# config-bank7.net
KiCad netlist of a schematic drawn in Altium Designer
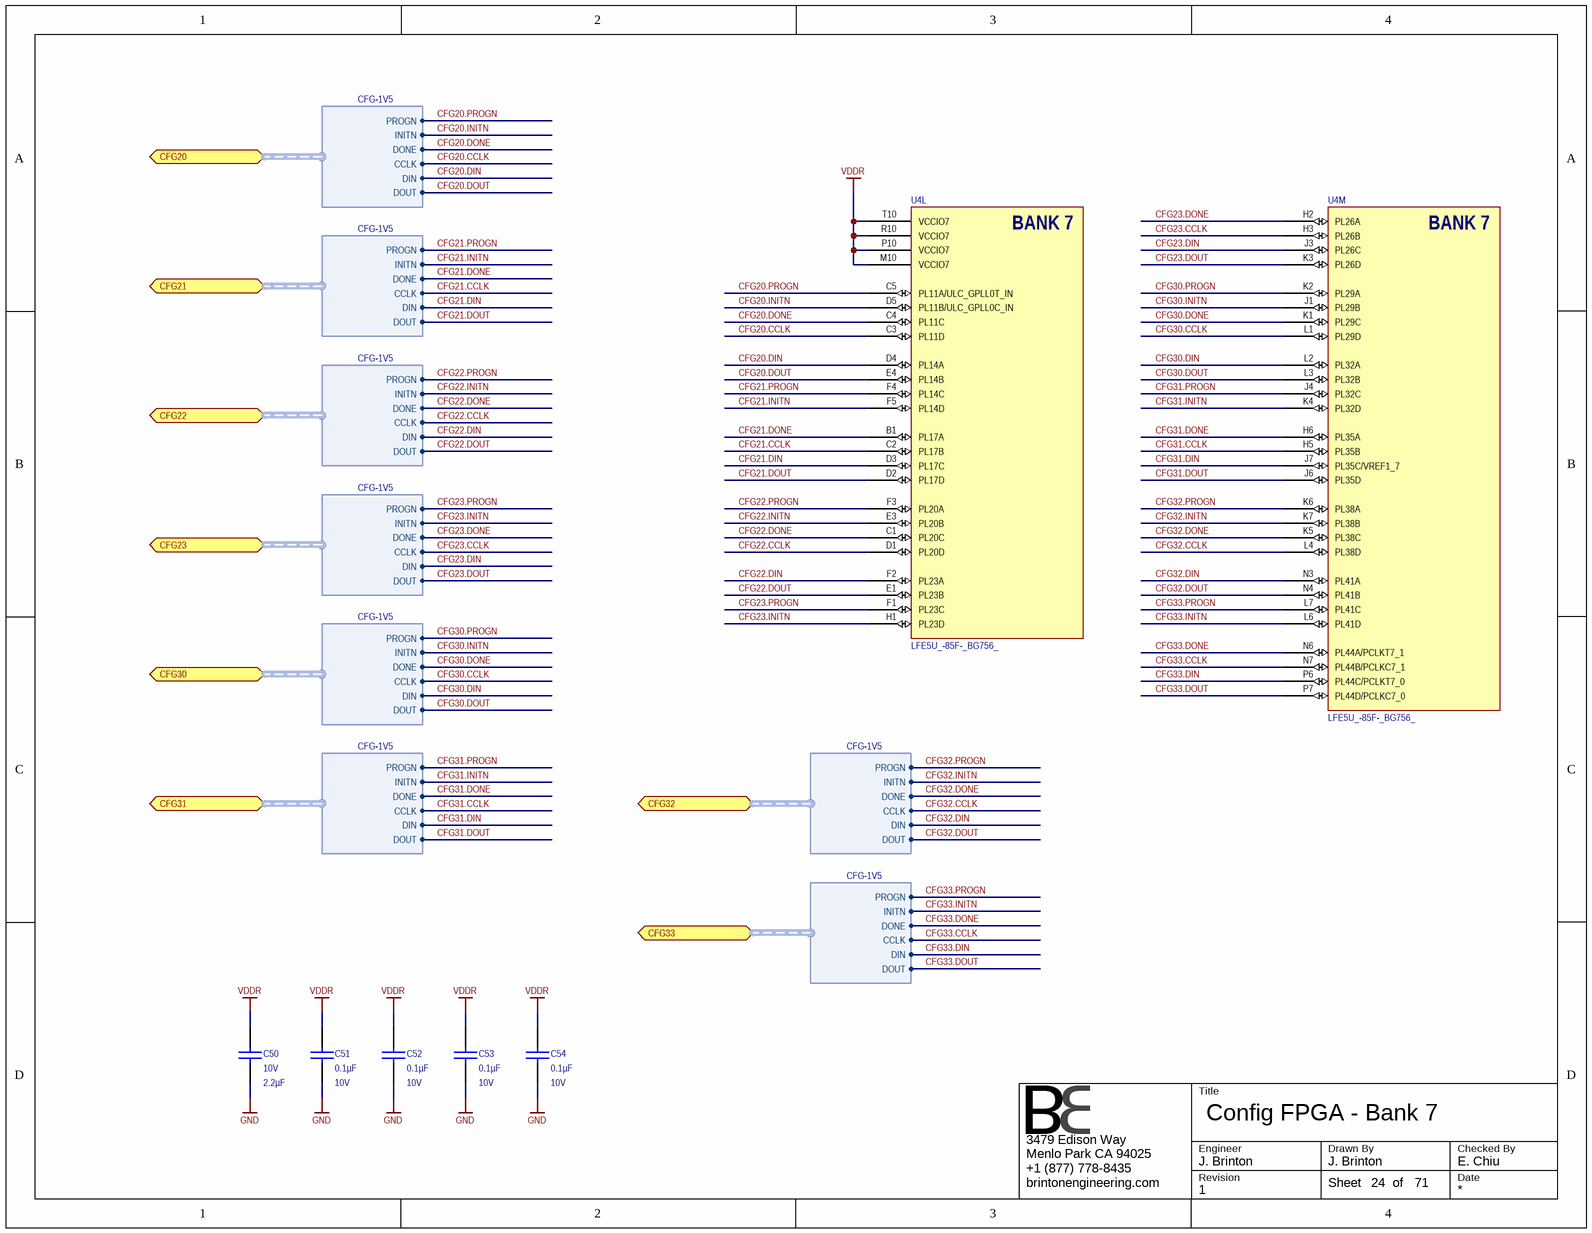
[diagram p0: config-bank7.SchDoc]

(export (version "E")
  (design (tool "Eeschema 10.0.6"))
  (components
    (comp (ref "C50")
      (value "GRM188R71A225KE15D")
      (footprint "CAPC1608X90N")
      (description "CAP CER 2.2UF 10V 10% X7R 0603")
      (fields
        (field (name "MANUFACTURER") "Murata Electronics North America")
        (field (name "TOLERANCE") "±10%")
        (field (name "VOLTAGE - RATED") "10V")
        (field (name "CAPACITANCE") "2.2µF")
      )
      (libsource (lib "murata") (part "GRM188R71A225KE15D"))
    )
    (comp (ref "C51")
      (value "GRM155R71A104KA01J")
      (footprint "CAPC1005X56N")
      (description "CAP CER 0.1UF 10V 10% X7R 0402")
      (fields
        (field (name "MANUFACTURER") "Murata Electronics North America")
        (field (name "TOLERANCE") "±10%")
        (field (name "CAPACITANCE") "0.1µF")
        (field (name "VOLTAGE - RATED") "10V")
      )
      (libsource (lib "murata") (part "GRM155R71A104KA01J"))
    )
    (comp (ref "C52")
      (value "GRM155R71A104KA01J")
      (footprint "CAPC1005X56N")
      (description "CAP CER 0.1UF 10V 10% X7R 0402")
      (fields
        (field (name "MANUFACTURER") "Murata Electronics North America")
        (field (name "TOLERANCE") "±10%")
        (field (name "CAPACITANCE") "0.1µF")
        (field (name "VOLTAGE - RATED") "10V")
      )
      (libsource (lib "murata") (part "GRM155R71A104KA01J"))
    )
    (comp (ref "C53")
      (value "GRM155R71A104KA01J")
      (footprint "CAPC1005X56N")
      (description "CAP CER 0.1UF 10V 10% X7R 0402")
      (fields
        (field (name "MANUFACTURER") "Murata Electronics North America")
        (field (name "TOLERANCE") "±10%")
        (field (name "CAPACITANCE") "0.1µF")
        (field (name "VOLTAGE - RATED") "10V")
      )
      (libsource (lib "murata") (part "GRM155R71A104KA01J"))
    )
    (comp (ref "C54")
      (value "GRM155R71A104KA01J")
      (footprint "CAPC1005X56N")
      (description "CAP CER 0.1UF 10V 10% X7R 0402")
      (fields
        (field (name "MANUFACTURER") "Murata Electronics North America")
        (field (name "TOLERANCE") "±10%")
        (field (name "CAPACITANCE") "0.1µF")
        (field (name "VOLTAGE - RATED") "10V")
      )
      (libsource (lib "murata") (part "GRM155R71A104KA01J"))
    )
    (comp (ref "U4")
      (value "LFE5U_-85F-_BG756_")
      (footprint "lattice:caBGA756")
      (description "ECP5 FPGA, 85k LUT, 756-caBGA")
      (fields (field (name "MANUFACTURER") "Lattice Semiconductor"))
      (libsource (lib "lattice") (part "LFE5U_-85F-_BG756_"))
    )
  )
  (nets
    (net (code "2") (name "/CFG20.CCLK") (class "Default")
      (node (ref "U4") (pin "C3") (pinfunction "PL11D_C3") (pintype "bidirectional"))
    )
    (net (code "3") (name "/CFG20.DIN") (class "Default")
      (node (ref "U4") (pin "D4") (pinfunction "PL14A_D4") (pintype "bidirectional"))
    )
    (net (code "4") (name "/CFG20.DONE") (class "Default")
      (node (ref "U4") (pin "C4") (pinfunction "PL11C_C4") (pintype "bidirectional"))
    )
    (net (code "5") (name "/CFG20.DOUT") (class "Default")
      (node (ref "U4") (pin "E4") (pinfunction "PL14B_E4") (pintype "bidirectional"))
    )
    (net (code "6") (name "/CFG20.INITN") (class "Default")
      (node (ref "U4") (pin "D5") (pinfunction "PL11B/ULC_GPLL0C_IN_D5") (pintype "bidirectional"))
    )
    (net (code "7") (name "/CFG20.PROGN") (class "Default")
      (node (ref "U4") (pin "C5") (pinfunction "PL11A/ULC_GPLL0T_IN_C5") (pintype "bidirectional"))
    )
    (net (code "8") (name "/CFG21.CCLK") (class "Default")
      (node (ref "U4") (pin "C2") (pinfunction "PL17B_C2") (pintype "bidirectional"))
    )
    (net (code "9") (name "/CFG21.DIN") (class "Default")
      (node (ref "U4") (pin "D3") (pinfunction "PL17C_D3") (pintype "bidirectional"))
    )
    (net (code "10") (name "/CFG21.DONE") (class "Default")
      (node (ref "U4") (pin "B1") (pinfunction "PL17A_B1") (pintype "bidirectional"))
    )
    (net (code "11") (name "/CFG21.DOUT") (class "Default")
      (node (ref "U4") (pin "D2") (pinfunction "PL17D_D2") (pintype "bidirectional"))
    )
    (net (code "12") (name "/CFG21.INITN") (class "Default")
      (node (ref "U4") (pin "F5") (pinfunction "PL14D_F5") (pintype "bidirectional"))
    )
    (net (code "13") (name "/CFG21.PROGN") (class "Default")
      (node (ref "U4") (pin "F4") (pinfunction "PL14C_F4") (pintype "bidirectional"))
    )
    (net (code "14") (name "/CFG22.CCLK") (class "Default")
      (node (ref "U4") (pin "D1") (pinfunction "PL20D_D1") (pintype "bidirectional"))
    )
    (net (code "15") (name "/CFG22.DIN") (class "Default")
      (node (ref "U4") (pin "F2") (pinfunction "PL23A_F2") (pintype "bidirectional"))
    )
    (net (code "16") (name "/CFG22.DONE") (class "Default")
      (node (ref "U4") (pin "C1") (pinfunction "PL20C_C1") (pintype "bidirectional"))
    )
    (net (code "17") (name "/CFG22.DOUT") (class "Default")
      (node (ref "U4") (pin "E1") (pinfunction "PL23B_E1") (pintype "bidirectional"))
    )
    (net (code "18") (name "/CFG22.INITN") (class "Default")
      (node (ref "U4") (pin "E3") (pinfunction "PL20B_E3") (pintype "bidirectional"))
    )
    (net (code "19") (name "/CFG22.PROGN") (class "Default")
      (node (ref "U4") (pin "F3") (pinfunction "PL20A_F3") (pintype "bidirectional"))
    )
    (net (code "20") (name "/CFG23.CCLK") (class "Default")
      (node (ref "U4") (pin "H3") (pinfunction "PL26B_H3") (pintype "bidirectional"))
    )
    (net (code "21") (name "/CFG23.DIN") (class "Default")
      (node (ref "U4") (pin "J3") (pinfunction "PL26C_J3") (pintype "bidirectional"))
    )
    (net (code "22") (name "/CFG23.DONE") (class "Default")
      (node (ref "U4") (pin "H2") (pinfunction "PL26A_H2") (pintype "bidirectional"))
    )
    (net (code "23") (name "/CFG23.DOUT") (class "Default")
      (node (ref "U4") (pin "K3") (pinfunction "PL26D_K3") (pintype "bidirectional"))
    )
    (net (code "24") (name "/CFG23.INITN") (class "Default")
      (node (ref "U4") (pin "H1") (pinfunction "PL23D_H1") (pintype "bidirectional"))
    )
    (net (code "25") (name "/CFG23.PROGN") (class "Default")
      (node (ref "U4") (pin "F1") (pinfunction "PL23C_F1") (pintype "bidirectional"))
    )
    (net (code "26") (name "/CFG30.CCLK") (class "Default")
      (node (ref "U4") (pin "L1") (pinfunction "PL29D_L1") (pintype "bidirectional"))
    )
    (net (code "27") (name "/CFG30.DIN") (class "Default")
      (node (ref "U4") (pin "L2") (pinfunction "PL32A_L2") (pintype "bidirectional"))
    )
    (net (code "28") (name "/CFG30.DONE") (class "Default")
      (node (ref "U4") (pin "K1") (pinfunction "PL29C_K1") (pintype "bidirectional"))
    )
    (net (code "29") (name "/CFG30.DOUT") (class "Default")
      (node (ref "U4") (pin "L3") (pinfunction "PL32B_L3") (pintype "bidirectional"))
    )
    (net (code "30") (name "/CFG30.INITN") (class "Default")
      (node (ref "U4") (pin "J1") (pinfunction "PL29B_J1") (pintype "bidirectional"))
    )
    (net (code "31") (name "/CFG30.PROGN") (class "Default")
      (node (ref "U4") (pin "K2") (pinfunction "PL29A_K2") (pintype "bidirectional"))
    )
    (net (code "32") (name "/CFG31.CCLK") (class "Default")
      (node (ref "U4") (pin "H5") (pinfunction "PL35B_H5") (pintype "bidirectional"))
    )
    (net (code "33") (name "/CFG31.DIN") (class "Default")
      (node (ref "U4") (pin "J7") (pinfunction "PL35C/VREF1_7_J7") (pintype "bidirectional"))
    )
    (net (code "34") (name "/CFG31.DONE") (class "Default")
      (node (ref "U4") (pin "H6") (pinfunction "PL35A_H6") (pintype "bidirectional"))
    )
    (net (code "35") (name "/CFG31.DOUT") (class "Default")
      (node (ref "U4") (pin "J6") (pinfunction "PL35D_J6") (pintype "bidirectional"))
    )
    (net (code "36") (name "/CFG31.INITN") (class "Default")
      (node (ref "U4") (pin "K4") (pinfunction "PL32D_K4") (pintype "bidirectional"))
    )
    (net (code "37") (name "/CFG31.PROGN") (class "Default")
      (node (ref "U4") (pin "J4") (pinfunction "PL32C_J4") (pintype "bidirectional"))
    )
    (net (code "38") (name "/CFG32.CCLK") (class "Default")
      (node (ref "U4") (pin "L4") (pinfunction "PL38D_L4") (pintype "bidirectional"))
    )
    (net (code "39") (name "/CFG32.DIN") (class "Default")
      (node (ref "U4") (pin "N3") (pinfunction "PL41A_N3") (pintype "bidirectional"))
    )
    (net (code "40") (name "/CFG32.DONE") (class "Default")
      (node (ref "U4") (pin "K5") (pinfunction "PL38C_K5") (pintype "bidirectional"))
    )
    (net (code "41") (name "/CFG32.DOUT") (class "Default")
      (node (ref "U4") (pin "N4") (pinfunction "PL41B_N4") (pintype "bidirectional"))
    )
    (net (code "42") (name "/CFG32.INITN") (class "Default")
      (node (ref "U4") (pin "K7") (pinfunction "PL38B_K7") (pintype "bidirectional"))
    )
    (net (code "43") (name "/CFG32.PROGN") (class "Default")
      (node (ref "U4") (pin "K6") (pinfunction "PL38A_K6") (pintype "bidirectional"))
    )
    (net (code "44") (name "/CFG33.CCLK") (class "Default")
      (node (ref "U4") (pin "N7") (pinfunction "PL44B/PCLKC7_1_N7") (pintype "bidirectional"))
    )
    (net (code "45") (name "/CFG33.DIN") (class "Default")
      (node (ref "U4") (pin "P6") (pinfunction "PL44C/PCLKT7_0_P6") (pintype "bidirectional"))
    )
    (net (code "46") (name "/CFG33.DONE") (class "Default")
      (node (ref "U4") (pin "N6") (pinfunction "PL44A/PCLKT7_1_N6") (pintype "bidirectional"))
    )
    (net (code "47") (name "/CFG33.DOUT") (class "Default")
      (node (ref "U4") (pin "P7") (pinfunction "PL44D/PCLKC7_0_P7") (pintype "bidirectional"))
    )
    (net (code "48") (name "/CFG33.INITN") (class "Default")
      (node (ref "U4") (pin "L6") (pinfunction "PL41D_L6") (pintype "bidirectional"))
    )
    (net (code "49") (name "/CFG33.PROGN") (class "Default")
      (node (ref "U4") (pin "L7") (pinfunction "PL41C_L7") (pintype "bidirectional"))
    )
    (net (code "51") (name "GND") (class "Default")
      (node (ref "C50") (pin "1") (pinfunction "1_1") (pintype "passive"))
      (node (ref "C51") (pin "1") (pinfunction "1_1") (pintype "passive"))
      (node (ref "C52") (pin "1") (pinfunction "1_1") (pintype "passive"))
      (node (ref "C53") (pin "1") (pinfunction "1_1") (pintype "passive"))
      (node (ref "C54") (pin "1") (pinfunction "1_1") (pintype "passive"))
    )
    (net (code "52") (name "VDDR") (class "Default")
      (node (ref "C50") (pin "2") (pinfunction "2_2") (pintype "passive"))
      (node (ref "C51") (pin "2") (pinfunction "2_2") (pintype "passive"))
      (node (ref "C52") (pin "2") (pinfunction "2_2") (pintype "passive"))
      (node (ref "C53") (pin "2") (pinfunction "2_2") (pintype "passive"))
      (node (ref "C54") (pin "2") (pinfunction "2_2") (pintype "passive"))
      (node (ref "U4") (pin "M10") (pinfunction "VCCIO7_M10") (pintype "power_in"))
      (node (ref "U4") (pin "P10") (pinfunction "VCCIO7_P10") (pintype "power_in"))
      (node (ref "U4") (pin "R10") (pinfunction "VCCIO7_R10") (pintype "power_in"))
      (node (ref "U4") (pin "T10") (pinfunction "VCCIO7_T10") (pintype "power_in"))
    )
  )
)
